# rp2040-mlx90393_1.net
KiCad netlist of a schematic drawn in EasyEDA Pro
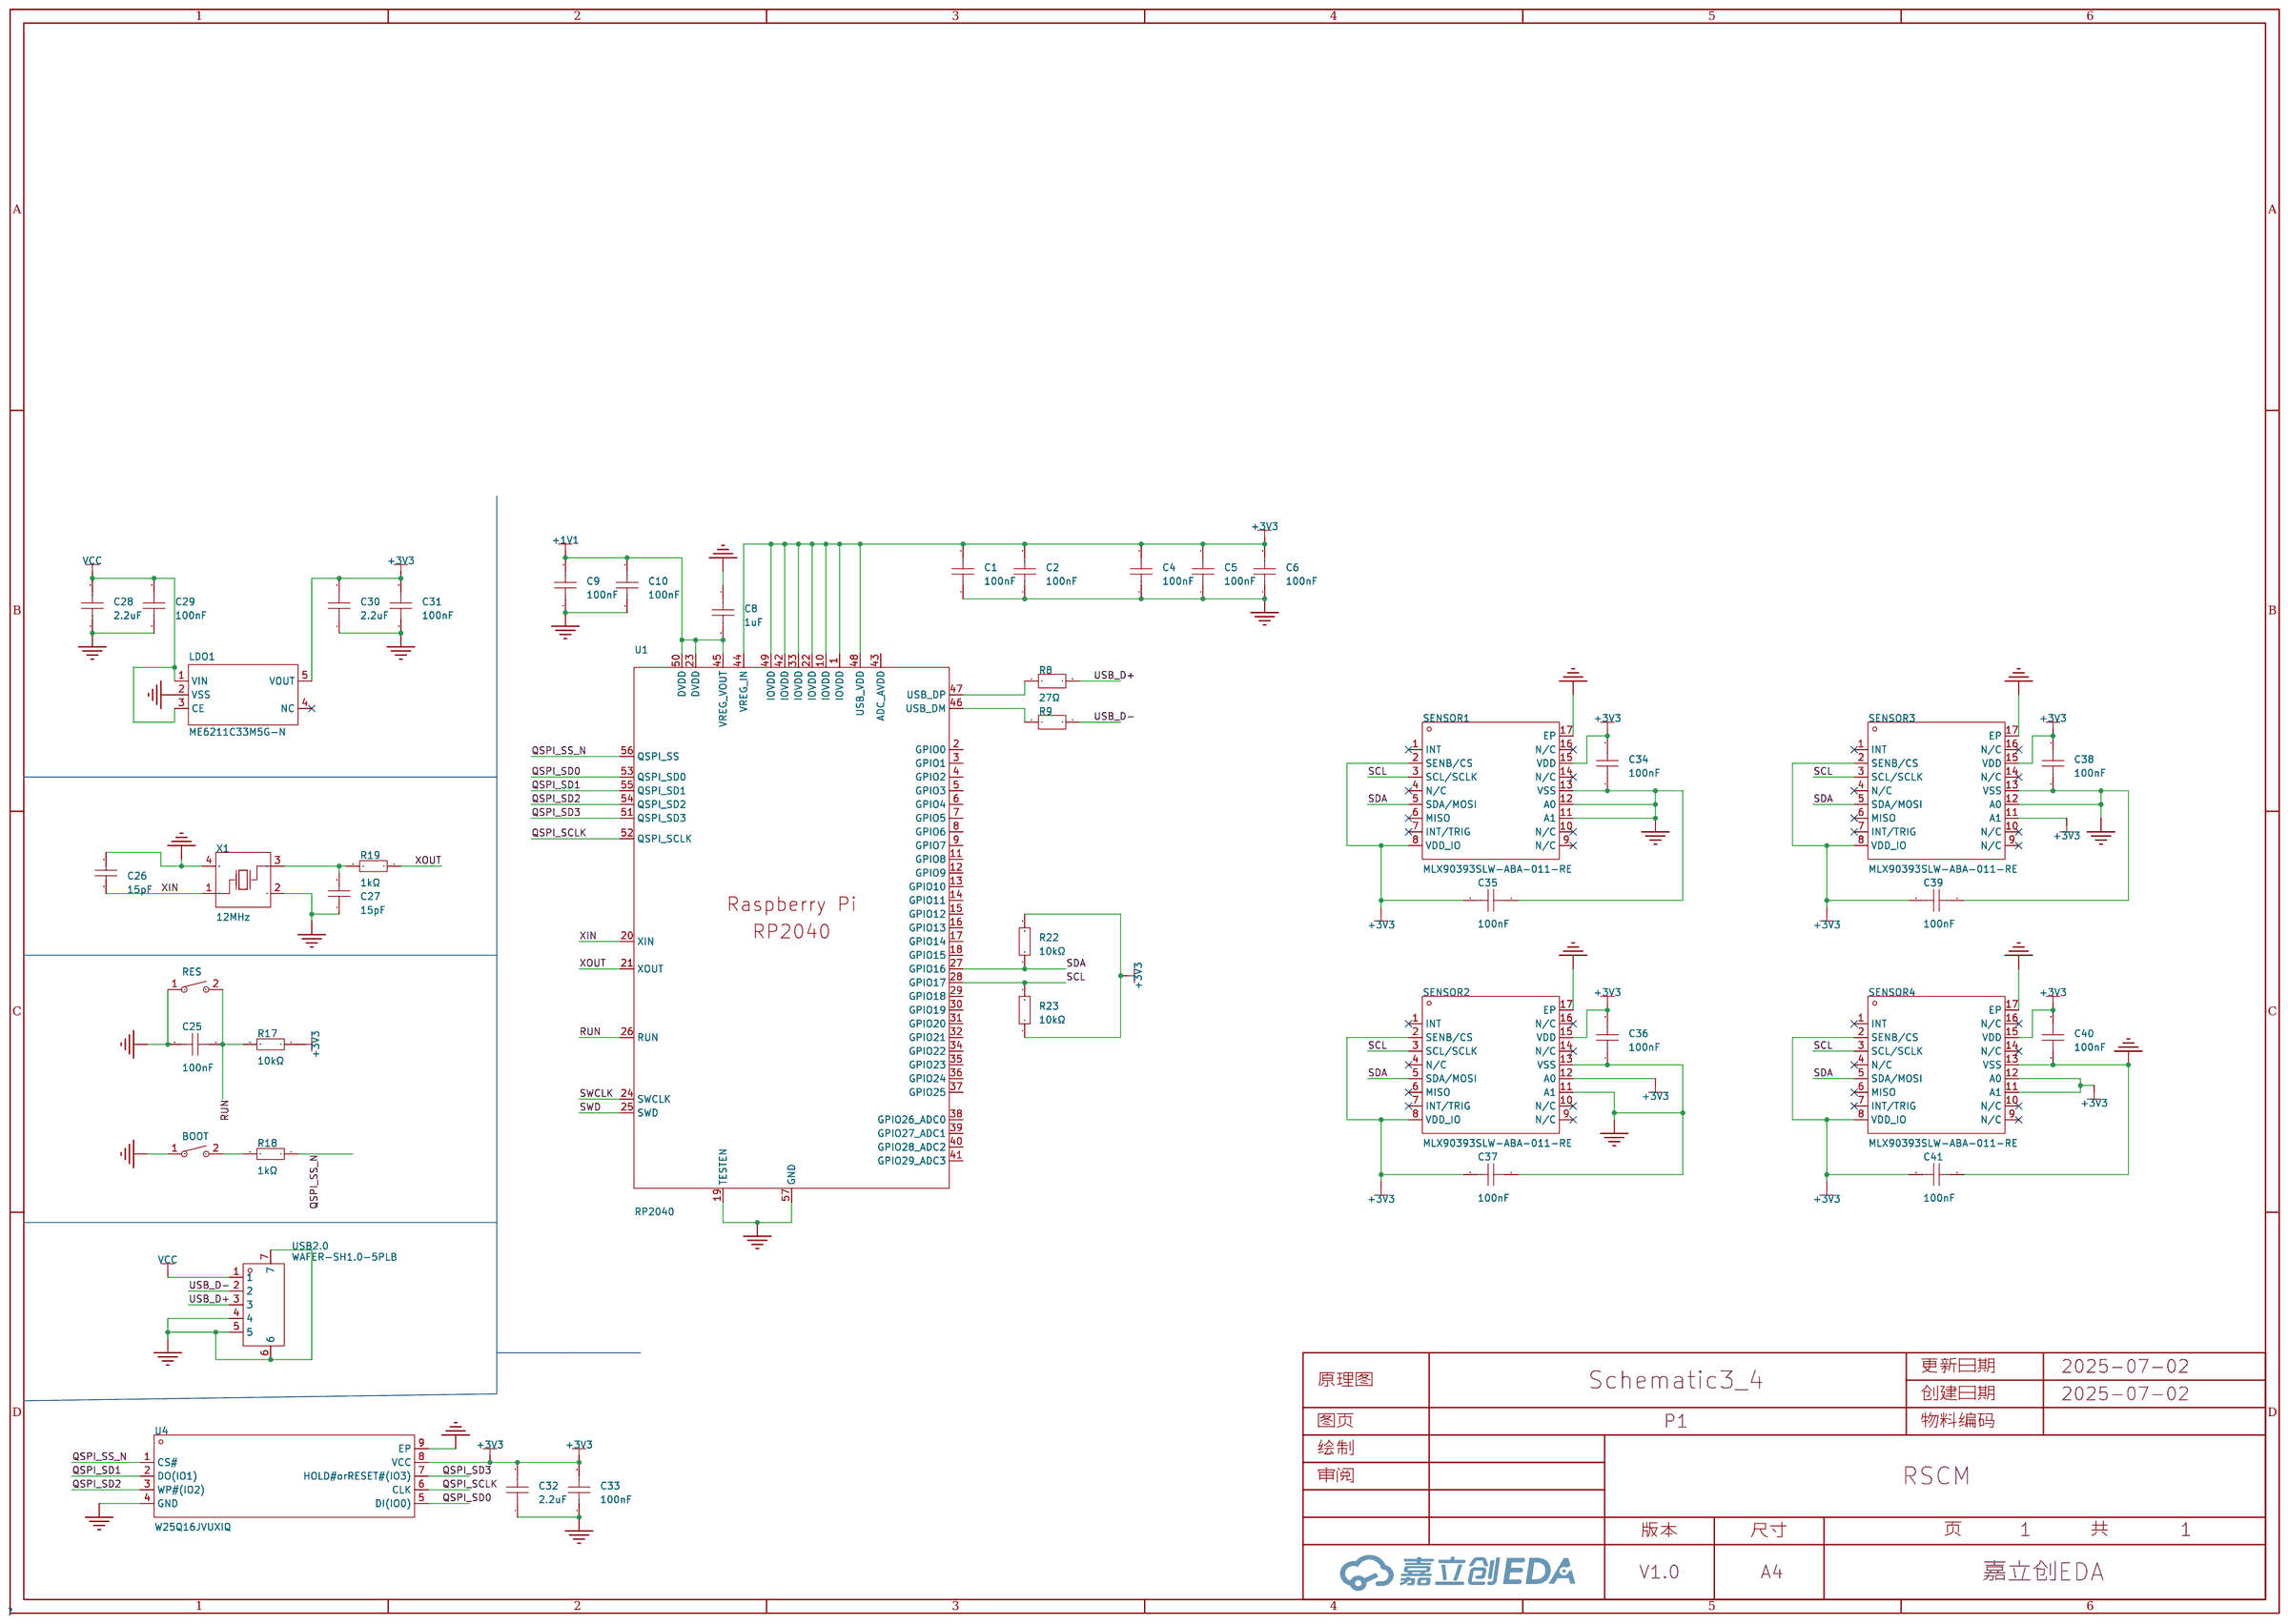
[diagram p0: schematic sheet]

(export (version "E")
  (design (tool "Eeschema 10.0.6"))
  (components
    (comp (ref "BOOT")
      (value "TS-1071AD-A1B3-D4")
      (footprint "easyedapro:SW-SMD_L4.0-W3.0-LS4.8")
      (description "电路结构:单刀单掷;安装方式:-;按钮形状:圆形按钮;带灯:-;作用力:250gf@±30gf;开关长度:4mm;开关宽度:3mm;开关高度:2mm;")
      (fields (field (name "Manufacturer") "Yuandi(元迪)"))
      (libsource (lib "easyedapro") (part "TS-1071AD-A1B3-D4"))
    )
    (comp (ref "C1")
      (value "100nF")
      (footprint "easyedapro:C0603")
      (description "容值:100nF;精度:±10%;额定电压:50V;材质(温度系数):X7R;")
      (fields
        (field (name "Manufacturer Part") "CGA0603X7R104K500JT")
        (field (name "Manufacturer") "HRE(芯声)")
      )
      (libsource (lib "easyedapro") (part "CGA0603X7R104K500JT"))
    )
    (comp (ref "C2")
      (value "100nF")
      (footprint "easyedapro:C0603")
      (description "容值:100nF;精度:±10%;额定电压:50V;材质(温度系数):X7R;")
      (fields
        (field (name "Manufacturer Part") "CGA0603X7R104K500JT")
        (field (name "Manufacturer") "HRE(芯声)")
      )
      (libsource (lib "easyedapro") (part "CGA0603X7R104K500JT"))
    )
    (comp (ref "C4")
      (value "100nF")
      (footprint "easyedapro:C0603")
      (description "容值:100nF;精度:±10%;额定电压:50V;材质(温度系数):X7R;")
      (fields
        (field (name "Manufacturer Part") "CGA0603X7R104K500JT")
        (field (name "Manufacturer") "HRE(芯声)")
      )
      (libsource (lib "easyedapro") (part "CGA0603X7R104K500JT"))
    )
    (comp (ref "C5")
      (value "100nF")
      (footprint "easyedapro:C0603")
      (description "容值:100nF;精度:±10%;额定电压:50V;材质(温度系数):X7R;")
      (fields
        (field (name "Manufacturer Part") "CGA0603X7R104K500JT")
        (field (name "Manufacturer") "HRE(芯声)")
      )
      (libsource (lib "easyedapro") (part "CGA0603X7R104K500JT"))
    )
    (comp (ref "C6")
      (value "100nF")
      (footprint "easyedapro:C0603")
      (description "容值:100nF;精度:±10%;额定电压:50V;材质(温度系数):X7R;")
      (fields
        (field (name "Manufacturer Part") "CGA0603X7R104K500JT")
        (field (name "Manufacturer") "HRE(芯声)")
      )
      (libsource (lib "easyedapro") (part "CGA0603X7R104K500JT"))
    )
    (comp (ref "C8")
      (value "1uF")
      (footprint "easyedapro:C0603")
      (description "容值:1uF;精度:±10%;额定电压:50V;温度系数:X5R;")
      (fields
        (field (name "Manufacturer Part") "CGA0603X5R105K500JT")
        (field (name "Manufacturer") "HRE(芯声)")
      )
      (libsource (lib "easyedapro") (part "CGA0603X5R105K500JT"))
    )
    (comp (ref "C9")
      (value "100nF")
      (footprint "easyedapro:C0603")
      (description "容值:100nF;精度:±10%;额定电压:50V;材质(温度系数):X7R;")
      (fields
        (field (name "Manufacturer Part") "CGA0603X7R104K500JT")
        (field (name "Manufacturer") "HRE(芯声)")
      )
      (libsource (lib "easyedapro") (part "CGA0603X7R104K500JT"))
    )
    (comp (ref "C10")
      (value "100nF")
      (footprint "easyedapro:C0603")
      (description "容值:100nF;精度:±10%;额定电压:50V;材质(温度系数):X7R;")
      (fields
        (field (name "Manufacturer Part") "CGA0603X7R104K500JT")
        (field (name "Manufacturer") "HRE(芯声)")
      )
      (libsource (lib "easyedapro") (part "CGA0603X7R104K500JT"))
    )
    (comp (ref "C25")
      (value "100nF")
      (footprint "easyedapro:C0603")
      (description "容值:100nF;精度:±10%;额定电压:50V;材质(温度系数):X7R;")
      (fields
        (field (name "Manufacturer Part") "CGA0603X7R104K500JT")
        (field (name "Manufacturer") "HRE(芯声)")
      )
      (libsource (lib "easyedapro") (part "CGA0603X7R104K500JT"))
    )
    (comp (ref "C26")
      (value "15pF")
      (footprint "easyedapro:C0603")
      (description "容值:15pF;精度:±5%;额定电压:50V;材质(温度系数):NP0;")
      (fields
        (field (name "Manufacturer Part") "CC0603JRNPO9BN150")
        (field (name "Manufacturer") "YAGEO(国巨)")
      )
      (libsource (lib "easyedapro") (part "CC0603JRNPO9BN150"))
    )
    (comp (ref "C27")
      (value "15pF")
      (footprint "easyedapro:C0603")
      (description "容值:15pF;精度:±5%;额定电压:50V;材质(温度系数):NP0;")
      (fields
        (field (name "Manufacturer Part") "CC0603JRNPO9BN150")
        (field (name "Manufacturer") "YAGEO(国巨)")
      )
      (libsource (lib "easyedapro") (part "CC0603JRNPO9BN150"))
    )
    (comp (ref "C28")
      (value "2.2uF")
      (footprint "easyedapro:C0603")
      (description "容值:2.2uF;精度:±10%;额定电压:50V;材质(温度系数):X5R;")
      (fields
        (field (name "Manufacturer Part") "CL10A225KB8NNNC")
        (field (name "Manufacturer") "SAMSUNG(三星)")
      )
      (libsource (lib "easyedapro") (part "CL10A225KB8NNNC"))
    )
    (comp (ref "C29")
      (value "100nF")
      (footprint "easyedapro:C0603")
      (description "容值:100nF;精度:±10%;额定电压:50V;材质(温度系数):X7R;")
      (fields
        (field (name "Manufacturer Part") "CGA0603X7R104K500JT")
        (field (name "Manufacturer") "HRE(芯声)")
      )
      (libsource (lib "easyedapro") (part "CGA0603X7R104K500JT"))
    )
    (comp (ref "C30")
      (value "2.2uF")
      (footprint "easyedapro:C0603")
      (description "容值:2.2uF;精度:±10%;额定电压:50V;材质(温度系数):X5R;")
      (fields
        (field (name "Manufacturer Part") "CL10A225KB8NNNC")
        (field (name "Manufacturer") "SAMSUNG(三星)")
      )
      (libsource (lib "easyedapro") (part "CL10A225KB8NNNC"))
    )
    (comp (ref "C31")
      (value "100nF")
      (footprint "easyedapro:C0603")
      (description "容值:100nF;精度:±10%;额定电压:50V;材质(温度系数):X7R;")
      (fields
        (field (name "Manufacturer Part") "CGA0603X7R104K500JT")
        (field (name "Manufacturer") "HRE(芯声)")
      )
      (libsource (lib "easyedapro") (part "CGA0603X7R104K500JT"))
    )
    (comp (ref "C32")
      (value "2.2uF")
      (footprint "easyedapro:C0603")
      (description "容值:2.2uF;精度:±10%;额定电压:50V;材质(温度系数):X5R;")
      (fields
        (field (name "Manufacturer Part") "CL10A225KB8NNNC")
        (field (name "Manufacturer") "SAMSUNG(三星)")
      )
      (libsource (lib "easyedapro") (part "CL10A225KB8NNNC"))
    )
    (comp (ref "C33")
      (value "100nF")
      (footprint "easyedapro:C0603")
      (description "容值:100nF;精度:±10%;额定电压:50V;材质(温度系数):X7R;")
      (fields
        (field (name "Manufacturer Part") "CGA0603X7R104K500JT")
        (field (name "Manufacturer") "HRE(芯声)")
      )
      (libsource (lib "easyedapro") (part "CGA0603X7R104K500JT"))
    )
    (comp (ref "C34")
      (value "100nF")
      (footprint "easyedapro:C0603")
      (description "容值:100nF;精度:±10%;额定电压:50V;材质(温度系数):X7R;")
      (fields
        (field (name "Manufacturer Part") "CGA0603X7R104K500JT")
        (field (name "Manufacturer") "HRE(芯声)")
      )
      (libsource (lib "easyedapro") (part "CGA0603X7R104K500JT"))
    )
    (comp (ref "C35")
      (value "100nF")
      (footprint "easyedapro:C0603")
      (description "容值:100nF;精度:±10%;额定电压:50V;材质(温度系数):X7R;")
      (fields
        (field (name "Manufacturer Part") "CGA0603X7R104K500JT")
        (field (name "Manufacturer") "HRE(芯声)")
      )
      (libsource (lib "easyedapro") (part "CGA0603X7R104K500JT"))
    )
    (comp (ref "C36")
      (value "100nF")
      (footprint "easyedapro:C0603")
      (description "容值:100nF;精度:±10%;额定电压:50V;材质(温度系数):X7R;")
      (fields
        (field (name "Manufacturer Part") "CGA0603X7R104K500JT")
        (field (name "Manufacturer") "HRE(芯声)")
      )
      (libsource (lib "easyedapro") (part "CGA0603X7R104K500JT"))
    )
    (comp (ref "C37")
      (value "100nF")
      (footprint "easyedapro:C0603")
      (description "容值:100nF;精度:±10%;额定电压:50V;材质(温度系数):X7R;")
      (fields
        (field (name "Manufacturer Part") "CGA0603X7R104K500JT")
        (field (name "Manufacturer") "HRE(芯声)")
      )
      (libsource (lib "easyedapro") (part "CGA0603X7R104K500JT"))
    )
    (comp (ref "C38")
      (value "100nF")
      (footprint "easyedapro:C0603")
      (description "容值:100nF;精度:±10%;额定电压:50V;材质(温度系数):X7R;")
      (fields
        (field (name "Manufacturer Part") "CGA0603X7R104K500JT")
        (field (name "Manufacturer") "HRE(芯声)")
      )
      (libsource (lib "easyedapro") (part "CGA0603X7R104K500JT"))
    )
    (comp (ref "C39")
      (value "100nF")
      (footprint "easyedapro:C0603")
      (description "容值:100nF;精度:±10%;额定电压:50V;材质(温度系数):X7R;")
      (fields
        (field (name "Manufacturer Part") "CGA0603X7R104K500JT")
        (field (name "Manufacturer") "HRE(芯声)")
      )
      (libsource (lib "easyedapro") (part "CGA0603X7R104K500JT"))
    )
    (comp (ref "C40")
      (value "100nF")
      (footprint "easyedapro:C0603")
      (description "容值:100nF;精度:±10%;额定电压:50V;材质(温度系数):X7R;")
      (fields
        (field (name "Manufacturer Part") "CGA0603X7R104K500JT")
        (field (name "Manufacturer") "HRE(芯声)")
      )
      (libsource (lib "easyedapro") (part "CGA0603X7R104K500JT"))
    )
    (comp (ref "C41")
      (value "100nF")
      (footprint "easyedapro:C0603")
      (description "容值:100nF;精度:±10%;额定电压:50V;材质(温度系数):X7R;")
      (fields
        (field (name "Manufacturer Part") "CGA0603X7R104K500JT")
        (field (name "Manufacturer") "HRE(芯声)")
      )
      (libsource (lib "easyedapro") (part "CGA0603X7R104K500JT"))
    )
    (comp (ref "LDO1")
      (value "ME6211C33M5G-N")
      (footprint "easyedapro:SOT-23-5_L3.0-W1.7-P0.95-LS2.8-BL")
      (description "输出类型:固定;工作电压:6V;输出电压:3.3V;输出电流:500mA;电源纹波抑制比(PSRR):70dB@(1kHz)；62dB@(10kHz);输出极性:正极;")
      (fields (field (name "Manufacturer") "MICRONE(南京微盟)"))
      (libsource (lib "easyedapro") (part "ME6211C33M5G-N"))
    )
    (comp (ref "R8")
      (value "27Ω")
      (footprint "easyedapro:R0603")
      (description "电阻类型:厚膜电阻;阻值:27Ω;精度:±1%;功率:100mW;工作电压:75V;温度系数:±100ppm/°C;")
      (fields (field (name "Manufacturer Part") "FRC0603F27R0TS") (field (name "Manufacturer") "FOJAN(富捷)"))
      (libsource (lib "easyedapro") (part "FRC0603F27R0TS"))
    )
    (comp (ref "R9")
      (value "27Ω")
      (footprint "easyedapro:R0603")
      (description "电阻类型:厚膜电阻;阻值:27Ω;精度:±1%;功率:100mW;工作电压:75V;温度系数:±100ppm/°C;")
      (fields (field (name "Manufacturer Part") "FRC0603F27R0TS") (field (name "Manufacturer") "FOJAN(富捷)"))
      (libsource (lib "easyedapro") (part "FRC0603F27R0TS"))
    )
    (comp (ref "R17")
      (value "10kΩ")
      (footprint "easyedapro:R0603")
      (description "电阻类型:厚膜电阻;阻值:10kΩ;精度:±1%;功率:100mW;")
      (fields (field (name "Manufacturer Part") "RC0603FR-0710KL") (field (name "Manufacturer") "YAGEO(国巨)"))
      (libsource (lib "easyedapro") (part "RC0603FR-0710KL"))
    )
    (comp (ref "R18")
      (value "1kΩ")
      (footprint "easyedapro:R0603")
      (description "电阻类型:厚膜电阻;阻值:10kΩ;精度:±1%;功率:100mW;")
      (fields (field (name "Manufacturer Part") "RC0603FR-0710KL") (field (name "Manufacturer") "YAGEO(国巨)"))
      (libsource (lib "easyedapro") (part "RC0603FR-0710KL"))
    )
    (comp (ref "R19")
      (value "1kΩ")
      (footprint "easyedapro:R0603")
      (description "电阻类型:厚膜电阻;阻值:1kΩ;精度:±1%;功率:100mW;最大工作电压:75V;温度系数:±100ppm/°C;")
      (fields
        (field (name "Manufacturer Part") "0603WAF1001T5E")
        (field (name "Manufacturer") "UNI-ROYAL(厚声)")
      )
      (libsource (lib "easyedapro") (part "0603WAF1001T5E"))
    )
    (comp (ref "R22")
      (value "10kΩ")
      (footprint "easyedapro:R0603")
      (description "电阻类型:厚膜电阻;阻值:4.7kΩ;精度:±1%;功率:100mW;最大工作电压:75V;温度系数:±100ppm/°C;")
      (fields
        (field (name "Manufacturer Part") "0603WAF4701T5E")
        (field (name "Manufacturer") "UNI-ROYAL(厚声)")
      )
      (libsource (lib "easyedapro") (part "0603WAF4701T5E"))
    )
    (comp (ref "R23")
      (value "10kΩ")
      (footprint "easyedapro:R0603")
      (description "电阻类型:厚膜电阻;阻值:4.7kΩ;精度:±1%;功率:100mW;最大工作电压:75V;温度系数:±100ppm/°C;")
      (fields
        (field (name "Manufacturer Part") "0603WAF4701T5E")
        (field (name "Manufacturer") "UNI-ROYAL(厚声)")
      )
      (libsource (lib "easyedapro") (part "0603WAF4701T5E"))
    )
    (comp (ref "RES")
      (value "TS-1071AD-A1B3-D4")
      (footprint "easyedapro:SW-SMD_L4.0-W3.0-LS4.8")
      (description "电路结构:单刀单掷;安装方式:-;按钮形状:圆形按钮;带灯:-;作用力:250gf@±30gf;开关长度:4mm;开关宽度:3mm;开关高度:2mm;")
      (fields (field (name "Manufacturer") "Yuandi(元迪)"))
      (libsource (lib "easyedapro") (part "TS-1071AD-A1B3-D4"))
    )
    (comp (ref "SENSOR1")
      (value "MLX90393SLW-ABA-011-RE")
      (footprint "easyedapro:VQFN-16_L3.0-W3.0-P0.50-BL-EP1.7")
      (description "三轴磁传感器")
      (fields (field (name "Manufacturer") "Melexis(比利时迈来芯)"))
      (libsource (lib "easyedapro") (part "MLX90393SLW-ABA-011-RE"))
    )
    (comp (ref "SENSOR2")
      (value "MLX90393SLW-ABA-011-RE")
      (footprint "easyedapro:VQFN-16_L3.0-W3.0-P0.50-BL-EP1.7")
      (description "三轴磁传感器")
      (fields (field (name "Manufacturer") "Melexis(比利时迈来芯)"))
      (libsource (lib "easyedapro") (part "MLX90393SLW-ABA-011-RE"))
    )
    (comp (ref "SENSOR3")
      (value "MLX90393SLW-ABA-011-RE")
      (footprint "easyedapro:VQFN-16_L3.0-W3.0-P0.50-BL-EP1.7")
      (description "三轴磁传感器")
      (fields (field (name "Manufacturer") "Melexis(比利时迈来芯)"))
      (libsource (lib "easyedapro") (part "MLX90393SLW-ABA-011-RE"))
    )
    (comp (ref "SENSOR4")
      (value "MLX90393SLW-ABA-011-RE")
      (footprint "easyedapro:VQFN-16_L3.0-W3.0-P0.50-BL-EP1.7")
      (description "三轴磁传感器")
      (fields (field (name "Manufacturer") "Melexis(比利时迈来芯)"))
      (libsource (lib "easyedapro") (part "MLX90393SLW-ABA-011-RE"))
    )
    (comp (ref "U1")
      (value "RP2040")
      (footprint "easyedapro:LQFN-56_L7.0-W7.0-P0.4-EP")
      (description "CPU内核:-;CPU最大主频:133MHz;应用领域:-;")
      (fields (field (name "Manufacturer") "Raspberry Pi(树莓派)"))
      (libsource (lib "easyedapro") (part "RP2040"))
    )
    (comp (ref "U4")
      (value "W25Q16JVUXIQ")
      (footprint "easyedapro:USON-8_L3.0-W2.0-P0.50-BL-EP")
      (fields (field (name "Manufacturer") "WINBOND(华邦)"))
      (libsource (lib "easyedapro") (part "W25Q16JVUXIQ"))
    )
    (comp (ref "USB2.0")
      (value "WAFER-SH1.0-5PLB")
      (footprint "easyedapro:CONN-SMD-5P-P1.00_BM05B-SRSS-TB-LF-SN")
      (fields (field (name "Manufacturer") "XUNPU(讯普)"))
      (libsource (lib "easyedapro") (part "WAFER-SH1.0-5PLB"))
    )
    (comp (ref "X1")
      (value "12MHz")
      (footprint "easyedapro:OSC-SMD_4P-L3.2-W2.5-BL")
      (description "晶振类型:贴片晶振;频率:12MHz;常温频差:±10ppm;外接负载电容:20pF;频率稳定度(全温):±20ppm;")
      (fields (field (name "Manufacturer Part") "X322512MSB4SI") (field (name "Manufacturer") "YXC(扬兴晶振)"))
      (libsource (lib "easyedapro") (part "X322512MSB4SI"))
    )
  )
  (nets
    (net (code "1") (name "+1V1") (class "Default")
      (node (ref "C10") (pin "2") (pinfunction "2_2") (pintype "unspecified"))
      (node (ref "C8") (pin "2") (pinfunction "2_2") (pintype "unspecified"))
      (node (ref "C9") (pin "2") (pinfunction "2_2") (pintype "unspecified"))
      (node (ref "U1") (pin "23") (pinfunction "DVDD_23") (pintype "bidirectional"))
      (node (ref "U1") (pin "45") (pinfunction "VREG_VOUT_45") (pintype "bidirectional"))
      (node (ref "U1") (pin "50") (pinfunction "DVDD_50") (pintype "bidirectional"))
    )
    (net (code "2") (name "+3V3") (class "Default")
      (node (ref "C1") (pin "2") (pinfunction "2_2") (pintype "unspecified"))
      (node (ref "C2") (pin "2") (pinfunction "2_2") (pintype "unspecified"))
      (node (ref "C30") (pin "2") (pinfunction "2_2") (pintype "unspecified"))
      (node (ref "C31") (pin "2") (pinfunction "2_2") (pintype "unspecified"))
      (node (ref "C32") (pin "2") (pinfunction "2_2") (pintype "unspecified"))
      (node (ref "C33") (pin "2") (pinfunction "2_2") (pintype "unspecified"))
      (node (ref "C34") (pin "2") (pinfunction "2_2") (pintype "unspecified"))
      (node (ref "C35") (pin "2") (pinfunction "2_2") (pintype "unspecified"))
      (node (ref "C36") (pin "2") (pinfunction "2_2") (pintype "unspecified"))
      (node (ref "C37") (pin "2") (pinfunction "2_2") (pintype "unspecified"))
      (node (ref "C38") (pin "2") (pinfunction "2_2") (pintype "unspecified"))
      (node (ref "C39") (pin "2") (pinfunction "2_2") (pintype "unspecified"))
      (node (ref "C4") (pin "2") (pinfunction "2_2") (pintype "unspecified"))
      (node (ref "C40") (pin "2") (pinfunction "2_2") (pintype "unspecified"))
      (node (ref "C41") (pin "2") (pinfunction "2_2") (pintype "unspecified"))
      (node (ref "C5") (pin "2") (pinfunction "2_2") (pintype "unspecified"))
      (node (ref "C6") (pin "2") (pinfunction "2_2") (pintype "unspecified"))
      (node (ref "LDO1") (pin "5") (pinfunction "VOUT_5") (pintype "unspecified"))
      (node (ref "R17") (pin "1") (pinfunction "1_1") (pintype "input"))
      (node (ref "R22") (pin "2") (pinfunction "2_2") (pintype "input"))
      (node (ref "R23") (pin "1") (pinfunction "1_1") (pintype "input"))
      (node (ref "SENSOR1") (pin "15") (pinfunction "VDD_15") (pintype "unspecified"))
      (node (ref "SENSOR1") (pin "2") (pinfunction "SENB/CS_2") (pintype "unspecified"))
      (node (ref "SENSOR1") (pin "8") (pinfunction "VDD_IO_8") (pintype "unspecified"))
      (node (ref "SENSOR2") (pin "12") (pinfunction "A0_12") (pintype "unspecified"))
      (node (ref "SENSOR2") (pin "15") (pinfunction "VDD_15") (pintype "unspecified"))
      (node (ref "SENSOR2") (pin "2") (pinfunction "SENB/CS_2") (pintype "unspecified"))
      (node (ref "SENSOR2") (pin "8") (pinfunction "VDD_IO_8") (pintype "unspecified"))
      (node (ref "SENSOR3") (pin "11") (pinfunction "A1_11") (pintype "unspecified"))
      (node (ref "SENSOR3") (pin "15") (pinfunction "VDD_15") (pintype "unspecified"))
      (node (ref "SENSOR3") (pin "2") (pinfunction "SENB/CS_2") (pintype "unspecified"))
      (node (ref "SENSOR3") (pin "8") (pinfunction "VDD_IO_8") (pintype "unspecified"))
      (node (ref "SENSOR4") (pin "11") (pinfunction "A1_11") (pintype "unspecified"))
      (node (ref "SENSOR4") (pin "12") (pinfunction "A0_12") (pintype "unspecified"))
      (node (ref "SENSOR4") (pin "15") (pinfunction "VDD_15") (pintype "unspecified"))
      (node (ref "SENSOR4") (pin "2") (pinfunction "SENB/CS_2") (pintype "unspecified"))
      (node (ref "SENSOR4") (pin "8") (pinfunction "VDD_IO_8") (pintype "unspecified"))
      (node (ref "U1") (pin "1") (pinfunction "IOVDD_1") (pintype "bidirectional"))
      (node (ref "U1") (pin "10") (pinfunction "IOVDD_10") (pintype "bidirectional"))
      (node (ref "U1") (pin "22") (pinfunction "IOVDD_22") (pintype "bidirectional"))
      (node (ref "U1") (pin "33") (pinfunction "IOVDD_33") (pintype "bidirectional"))
      (node (ref "U1") (pin "42") (pinfunction "IOVDD_42") (pintype "bidirectional"))
      (node (ref "U1") (pin "44") (pinfunction "VREG_IN_44") (pintype "bidirectional"))
      (node (ref "U1") (pin "48") (pinfunction "USB_VDD_48") (pintype "bidirectional"))
      (node (ref "U1") (pin "49") (pinfunction "IOVDD_49") (pintype "bidirectional"))
      (node (ref "U4") (pin "8") (pinfunction "VCC_8") (pintype "unspecified"))
    )
    (net (code "3") (name "/QSPI_SCLK") (class "Default")
      (node (ref "U1") (pin "52") (pinfunction "QSPI_SCLK_52") (pintype "output"))
      (node (ref "U4") (pin "6") (pinfunction "CLK_6") (pintype "unspecified"))
    )
    (net (code "4") (name "/QSPI_SD0") (class "Default")
      (node (ref "U1") (pin "53") (pinfunction "QSPI_SD0_53") (pintype "bidirectional"))
      (node (ref "U4") (pin "5") (pinfunction "DI(IO0)_5") (pintype "unspecified"))
    )
    (net (code "5") (name "/QSPI_SD1") (class "Default")
      (node (ref "U1") (pin "55") (pinfunction "QSPI_SD1_55") (pintype "bidirectional"))
      (node (ref "U4") (pin "2") (pinfunction "DO(IO1)_2") (pintype "unspecified"))
    )
    (net (code "6") (name "/QSPI_SD2") (class "Default")
      (node (ref "U1") (pin "54") (pinfunction "QSPI_SD2_54") (pintype "bidirectional"))
      (node (ref "U4") (pin "3") (pinfunction "WP#(IO2)_3") (pintype "unspecified"))
    )
    (net (code "7") (name "/QSPI_SD3") (class "Default")
      (node (ref "U1") (pin "51") (pinfunction "QSPI_SD3_51") (pintype "bidirectional"))
      (node (ref "U4") (pin "7") (pinfunction "HOLD#orRESET#(IO3)_7") (pintype "unspecified"))
    )
    (net (code "8") (name "/QSPI_SS_N") (class "Default")
      (node (ref "R18") (pin "1") (pinfunction "1_1") (pintype "input"))
      (node (ref "U1") (pin "56") (pinfunction "QSPI_SS_56") (pintype "bidirectional"))
      (node (ref "U4") (pin "1") (pinfunction "CS#_1") (pintype "unspecified"))
    )
    (net (code "9") (name "/RUN") (class "Default")
      (node (ref "C25") (pin "2") (pinfunction "2_2") (pintype "unspecified"))
      (node (ref "R17") (pin "2") (pinfunction "2_2") (pintype "input"))
      (node (ref "RES") (pin "2") (pinfunction "2_2") (pintype "input"))
      (node (ref "U1") (pin "26") (pinfunction "RUN_26") (pintype "input"))
    )
    (net (code "10") (name "/SCL") (class "Default")
      (node (ref "R23") (pin "2") (pinfunction "2_2") (pintype "input"))
      (node (ref "SENSOR1") (pin "3") (pinfunction "SCL/SCLK_3") (pintype "unspecified"))
      (node (ref "SENSOR2") (pin "3") (pinfunction "SCL/SCLK_3") (pintype "unspecified"))
      (node (ref "SENSOR3") (pin "3") (pinfunction "SCL/SCLK_3") (pintype "unspecified"))
      (node (ref "SENSOR4") (pin "3") (pinfunction "SCL/SCLK_3") (pintype "unspecified"))
      (node (ref "U1") (pin "28") (pinfunction "GPIO17_28") (pintype "bidirectional"))
    )
    (net (code "11") (name "/SDA") (class "Default")
      (node (ref "R22") (pin "1") (pinfunction "1_1") (pintype "input"))
      (node (ref "SENSOR1") (pin "5") (pinfunction "SDA/MOSI_5") (pintype "unspecified"))
      (node (ref "SENSOR2") (pin "5") (pinfunction "SDA/MOSI_5") (pintype "unspecified"))
      (node (ref "SENSOR3") (pin "5") (pinfunction "SDA/MOSI_5") (pintype "unspecified"))
      (node (ref "SENSOR4") (pin "5") (pinfunction "SDA/MOSI_5") (pintype "unspecified"))
      (node (ref "U1") (pin "27") (pinfunction "GPIO16_27") (pintype "bidirectional"))
    )
    (net (code "12") (name "/SWCLK") (class "Default")
      (node (ref "U1") (pin "24") (pinfunction "SWCLK_24") (pintype "output"))
    )
    (net (code "13") (name "/SWD") (class "Default")
      (node (ref "U1") (pin "25") (pinfunction "SWD_25") (pintype "bidirectional"))
    )
    (net (code "14") (name "/USB_D+") (class "Default")
      (node (ref "R8") (pin "2") (pinfunction "2_2") (pintype "unspecified"))
      (node (ref "USB2.0") (pin "3") (pinfunction "3_3") (pintype "unspecified"))
    )
    (net (code "15") (name "/USB_D-") (class "Default")
      (node (ref "R9") (pin "2") (pinfunction "2_2") (pintype "unspecified"))
      (node (ref "USB2.0") (pin "2") (pinfunction "2_2") (pintype "unspecified"))
    )
    (net (code "16") (name "/XIN") (class "Default")
      (node (ref "C26") (pin "1") (pinfunction "1_1") (pintype "input"))
      (node (ref "U1") (pin "20") (pinfunction "XIN_20") (pintype "input"))
      (node (ref "X1") (pin "1") (pinfunction "OSC1_1") (pintype "unspecified"))
    )
    (net (code "17") (name "/XOUT") (class "Default")
      (node (ref "R19") (pin "1") (pinfunction "1_1") (pintype "input"))
      (node (ref "U1") (pin "21") (pinfunction "XOUT_21") (pintype "unspecified"))
    )
    (net (code "18") (name "GND") (class "Default")
      (node (ref "BOOT") (pin "1") (pinfunction "1_1") (pintype "input"))
      (node (ref "C1") (pin "1") (pinfunction "1_1") (pintype "unspecified"))
      (node (ref "C10") (pin "1") (pinfunction "1_1") (pintype "unspecified"))
      (node (ref "C2") (pin "1") (pinfunction "1_1") (pintype "unspecified"))
      (node (ref "C25") (pin "1") (pinfunction "1_1") (pintype "unspecified"))
      (node (ref "C26") (pin "2") (pinfunction "2_2") (pintype "input"))
      (node (ref "C27") (pin "1") (pinfunction "1_1") (pintype "input"))
      (node (ref "C28") (pin "1") (pinfunction "1_1") (pintype "unspecified"))
      (node (ref "C29") (pin "1") (pinfunction "1_1") (pintype "unspecified"))
      (node (ref "C30") (pin "1") (pinfunction "1_1") (pintype "unspecified"))
      (node (ref "C31") (pin "1") (pinfunction "1_1") (pintype "unspecified"))
      (node (ref "C32") (pin "1") (pinfunction "1_1") (pintype "unspecified"))
      (node (ref "C33") (pin "1") (pinfunction "1_1") (pintype "unspecified"))
      (node (ref "C34") (pin "1") (pinfunction "1_1") (pintype "unspecified"))
      (node (ref "C35") (pin "1") (pinfunction "1_1") (pintype "unspecified"))
      (node (ref "C36") (pin "1") (pinfunction "1_1") (pintype "unspecified"))
      (node (ref "C37") (pin "1") (pinfunction "1_1") (pintype "unspecified"))
      (node (ref "C38") (pin "1") (pinfunction "1_1") (pintype "unspecified"))
      (node (ref "C39") (pin "1") (pinfunction "1_1") (pintype "unspecified"))
      (node (ref "C4") (pin "1") (pinfunction "1_1") (pintype "unspecified"))
      (node (ref "C40") (pin "1") (pinfunction "1_1") (pintype "unspecified"))
      (node (ref "C41") (pin "1") (pinfunction "1_1") (pintype "unspecified"))
      (node (ref "C5") (pin "1") (pinfunction "1_1") (pintype "unspecified"))
      (node (ref "C6") (pin "1") (pinfunction "1_1") (pintype "unspecified"))
      (node (ref "C8") (pin "1") (pinfunction "1_1") (pintype "unspecified"))
      (node (ref "C9") (pin "1") (pinfunction "1_1") (pintype "unspecified"))
      (node (ref "LDO1") (pin "2") (pinfunction "VSS_2") (pintype "unspecified"))
      (node (ref "RES") (pin "1") (pinfunction "1_1") (pintype "input"))
      (node (ref "SENSOR1") (pin "11") (pinfunction "A1_11") (pintype "unspecified"))
      (node (ref "SENSOR1") (pin "12") (pinfunction "A0_12") (pintype "unspecified"))
      (node (ref "SENSOR1") (pin "13") (pinfunction "VSS_13") (pintype "unspecified"))
      (node (ref "SENSOR1") (pin "17") (pinfunction "EP_17") (pintype "unspecified"))
      (node (ref "SENSOR2") (pin "11") (pinfunction "A1_11") (pintype "unspecified"))
      (node (ref "SENSOR2") (pin "13") (pinfunction "VSS_13") (pintype "unspecified"))
      (node (ref "SENSOR2") (pin "17") (pinfunction "EP_17") (pintype "unspecified"))
      (node (ref "SENSOR3") (pin "12") (pinfunction "A0_12") (pintype "unspecified"))
      (node (ref "SENSOR3") (pin "13") (pinfunction "VSS_13") (pintype "unspecified"))
      (node (ref "SENSOR3") (pin "17") (pinfunction "EP_17") (pintype "unspecified"))
      (node (ref "SENSOR4") (pin "13") (pinfunction "VSS_13") (pintype "unspecified"))
      (node (ref "SENSOR4") (pin "17") (pinfunction "EP_17") (pintype "unspecified"))
      (node (ref "U1") (pin "19") (pinfunction "TESTEN_19") (pintype "unspecified"))
      (node (ref "U1") (pin "57") (pinfunction "GND_57") (pintype "bidirectional"))
      (node (ref "U4") (pin "4") (pinfunction "GND_4") (pintype "unspecified"))
      (node (ref "U4") (pin "9") (pinfunction "EP_9") (pintype "unspecified"))
      (node (ref "USB2.0") (pin "4") (pinfunction "4_4") (pintype "unspecified"))
      (node (ref "USB2.0") (pin "5") (pinfunction "5_5") (pintype "unspecified"))
      (node (ref "USB2.0") (pin "6") (pinfunction "6_6") (pintype "unspecified"))
      (node (ref "USB2.0") (pin "7") (pinfunction "7_7") (pintype "unspecified"))
      (node (ref "X1") (pin "2") (pinfunction "GND_2") (pintype "unspecified"))
      (node (ref "X1") (pin "4") (pinfunction "GND_4") (pintype "unspecified"))
    )
    (net (code "19") (name "Net-(BOOT-Pad2)") (class "Default")
      (node (ref "BOOT") (pin "2") (pinfunction "2_2") (pintype "input"))
      (node (ref "R18") (pin "2") (pinfunction "2_2") (pintype "input"))
    )
    (net (code "20") (name "Net-(U1-USB_DM)") (class "Default")
      (node (ref "R9") (pin "1") (pinfunction "1_1") (pintype "unspecified"))
      (node (ref "U1") (pin "46") (pinfunction "USB_DM_46") (pintype "bidirectional"))
    )
    (net (code "21") (name "Net-(U1-USB_DP)") (class "Default")
      (node (ref "R8") (pin "1") (pinfunction "1_1") (pintype "unspecified"))
      (node (ref "U1") (pin "47") (pinfunction "USB_DP_47") (pintype "bidirectional"))
    )
    (net (code "22") (name "Net-(X1-OSC2)") (class "Default")
      (node (ref "C27") (pin "2") (pinfunction "2_2") (pintype "input"))
      (node (ref "R19") (pin "2") (pinfunction "2_2") (pintype "input"))
      (node (ref "X1") (pin "3") (pinfunction "OSC2_3") (pintype "unspecified"))
    )
    (net (code "23") (name "VCC") (class "Default")
      (node (ref "C28") (pin "2") (pinfunction "2_2") (pintype "unspecified"))
      (node (ref "C29") (pin "2") (pinfunction "2_2") (pintype "unspecified"))
      (node (ref "LDO1") (pin "1") (pinfunction "VIN_1") (pintype "unspecified"))
      (node (ref "LDO1") (pin "3") (pinfunction "CE_3") (pintype "unspecified"))
      (node (ref "USB2.0") (pin "1") (pinfunction "1_1") (pintype "unspecified"))
    )
    (net (code "24") (name "unconnected-(LDO1-NC-Pad4)") (class "Default")
      (node (ref "LDO1") (pin "4") (pinfunction "NC_4") (pintype "unspecified+no_connect"))
    )
    (net (code "25") (name "unconnected-(SENSOR1-INT-Pad1)") (class "Default")
      (node (ref "SENSOR1") (pin "1") (pinfunction "INT_1") (pintype "unspecified+no_connect"))
    )
    (net (code "26") (name "unconnected-(SENSOR1-INT{slash}TRIG-Pad7)") (class "Default")
      (node (ref "SENSOR1") (pin "7") (pinfunction "INT/TRIG_7") (pintype "unspecified+no_connect"))
    )
    (net (code "27") (name "unconnected-(SENSOR1-MISO-Pad6)") (class "Default")
      (node (ref "SENSOR1") (pin "6") (pinfunction "MISO_6") (pintype "unspecified+no_connect"))
    )
    (net (code "28") (name "unconnected-(SENSOR1-N{slash}C-Pad4)") (class "Default")
      (node (ref "SENSOR1") (pin "4") (pinfunction "N/C_4") (pintype "unspecified+no_connect"))
    )
    (net (code "29") (name "unconnected-(SENSOR1-N{slash}C-Pad9)") (class "Default")
      (node (ref "SENSOR1") (pin "9") (pinfunction "N/C_9") (pintype "unspecified+no_connect"))
    )
    (net (code "30") (name "unconnected-(SENSOR1-N{slash}C-Pad10)") (class "Default")
      (node (ref "SENSOR1") (pin "10") (pinfunction "N/C_10") (pintype "unspecified+no_connect"))
    )
    (net (code "31") (name "unconnected-(SENSOR1-N{slash}C-Pad14)") (class "Default")
      (node (ref "SENSOR1") (pin "14") (pinfunction "N/C_14") (pintype "unspecified+no_connect"))
    )
    (net (code "32") (name "unconnected-(SENSOR1-N{slash}C-Pad16)") (class "Default")
      (node (ref "SENSOR1") (pin "16") (pinfunction "N/C_16") (pintype "unspecified+no_connect"))
    )
    (net (code "33") (name "unconnected-(SENSOR2-INT-Pad1)") (class "Default")
      (node (ref "SENSOR2") (pin "1") (pinfunction "INT_1") (pintype "unspecified+no_connect"))
    )
    (net (code "34") (name "unconnected-(SENSOR2-INT{slash}TRIG-Pad7)") (class "Default")
      (node (ref "SENSOR2") (pin "7") (pinfunction "INT/TRIG_7") (pintype "unspecified+no_connect"))
    )
    (net (code "35") (name "unconnected-(SENSOR2-MISO-Pad6)") (class "Default")
      (node (ref "SENSOR2") (pin "6") (pinfunction "MISO_6") (pintype "unspecified+no_connect"))
    )
    (net (code "36") (name "unconnected-(SENSOR2-N{slash}C-Pad4)") (class "Default")
      (node (ref "SENSOR2") (pin "4") (pinfunction "N/C_4") (pintype "unspecified+no_connect"))
    )
    (net (code "37") (name "unconnected-(SENSOR2-N{slash}C-Pad9)") (class "Default")
      (node (ref "SENSOR2") (pin "9") (pinfunction "N/C_9") (pintype "unspecified+no_connect"))
    )
    (net (code "38") (name "unconnected-(SENSOR2-N{slash}C-Pad10)") (class "Default")
      (node (ref "SENSOR2") (pin "10") (pinfunction "N/C_10") (pintype "unspecified+no_connect"))
    )
    (net (code "39") (name "unconnected-(SENSOR2-N{slash}C-Pad14)") (class "Default")
      (node (ref "SENSOR2") (pin "14") (pinfunction "N/C_14") (pintype "unspecified+no_connect"))
    )
    (net (code "40") (name "unconnected-(SENSOR2-N{slash}C-Pad16)") (class "Default")
      (node (ref "SENSOR2") (pin "16") (pinfunction "N/C_16") (pintype "unspecified+no_connect"))
    )
    (net (code "41") (name "unconnected-(SENSOR3-INT-Pad1)") (class "Default")
      (node (ref "SENSOR3") (pin "1") (pinfunction "INT_1") (pintype "unspecified+no_connect"))
    )
    (net (code "42") (name "unconnected-(SENSOR3-INT{slash}TRIG-Pad7)") (class "Default")
      (node (ref "SENSOR3") (pin "7") (pinfunction "INT/TRIG_7") (pintype "unspecified+no_connect"))
    )
    (net (code "43") (name "unconnected-(SENSOR3-MISO-Pad6)") (class "Default")
      (node (ref "SENSOR3") (pin "6") (pinfunction "MISO_6") (pintype "unspecified+no_connect"))
    )
    (net (code "44") (name "unconnected-(SENSOR3-N{slash}C-Pad4)") (class "Default")
      (node (ref "SENSOR3") (pin "4") (pinfunction "N/C_4") (pintype "unspecified+no_connect"))
    )
    (net (code "45") (name "unconnected-(SENSOR3-N{slash}C-Pad9)") (class "Default")
      (node (ref "SENSOR3") (pin "9") (pinfunction "N/C_9") (pintype "unspecified+no_connect"))
    )
    (net (code "46") (name "unconnected-(SENSOR3-N{slash}C-Pad10)") (class "Default")
      (node (ref "SENSOR3") (pin "10") (pinfunction "N/C_10") (pintype "unspecified+no_connect"))
    )
    (net (code "47") (name "unconnected-(SENSOR3-N{slash}C-Pad14)") (class "Default")
      (node (ref "SENSOR3") (pin "14") (pinfunction "N/C_14") (pintype "unspecified+no_connect"))
    )
    (net (code "48") (name "unconnected-(SENSOR3-N{slash}C-Pad16)") (class "Default")
      (node (ref "SENSOR3") (pin "16") (pinfunction "N/C_16") (pintype "unspecified+no_connect"))
    )
    (net (code "49") (name "unconnected-(SENSOR4-INT-Pad1)") (class "Default")
      (node (ref "SENSOR4") (pin "1") (pinfunction "INT_1") (pintype "unspecified+no_connect"))
    )
    (net (code "50") (name "unconnected-(SENSOR4-INT{slash}TRIG-Pad7)") (class "Default")
      (node (ref "SENSOR4") (pin "7") (pinfunction "INT/TRIG_7") (pintype "unspecified+no_connect"))
    )
    (net (code "51") (name "unconnected-(SENSOR4-MISO-Pad6)") (class "Default")
      (node (ref "SENSOR4") (pin "6") (pinfunction "MISO_6") (pintype "unspecified+no_connect"))
    )
    (net (code "52") (name "unconnected-(SENSOR4-N{slash}C-Pad4)") (class "Default")
      (node (ref "SENSOR4") (pin "4") (pinfunction "N/C_4") (pintype "unspecified+no_connect"))
    )
    (net (code "53") (name "unconnected-(SENSOR4-N{slash}C-Pad9)") (class "Default")
      (node (ref "SENSOR4") (pin "9") (pinfunction "N/C_9") (pintype "unspecified+no_connect"))
    )
    (net (code "54") (name "unconnected-(SENSOR4-N{slash}C-Pad10)") (class "Default")
      (node (ref "SENSOR4") (pin "10") (pinfunction "N/C_10") (pintype "unspecified+no_connect"))
    )
    (net (code "55") (name "unconnected-(SENSOR4-N{slash}C-Pad14)") (class "Default")
      (node (ref "SENSOR4") (pin "14") (pinfunction "N/C_14") (pintype "unspecified+no_connect"))
    )
    (net (code "56") (name "unconnected-(SENSOR4-N{slash}C-Pad16)") (class "Default")
      (node (ref "SENSOR4") (pin "16") (pinfunction "N/C_16") (pintype "unspecified+no_connect"))
    )
    (net (code "57") (name "unconnected-(U1-ADC_AVDD-Pad43)") (class "Default")
      (node (ref "U1") (pin "43") (pinfunction "ADC_AVDD_43") (pintype "bidirectional"))
    )
    (net (code "58") (name "unconnected-(U1-GPIO0-Pad2)") (class "Default")
      (node (ref "U1") (pin "2") (pinfunction "GPIO0_2") (pintype "bidirectional"))
    )
    (net (code "59") (name "unconnected-(U1-GPIO1-Pad3)") (class "Default")
      (node (ref "U1") (pin "3") (pinfunction "GPIO1_3") (pintype "bidirectional"))
    )
    (net (code "60") (name "unconnected-(U1-GPIO2-Pad4)") (class "Default")
      (node (ref "U1") (pin "4") (pinfunction "GPIO2_4") (pintype "bidirectional"))
    )
    (net (code "61") (name "unconnected-(U1-GPIO3-Pad5)") (class "Default")
      (node (ref "U1") (pin "5") (pinfunction "GPIO3_5") (pintype "bidirectional"))
    )
    (net (code "62") (name "unconnected-(U1-GPIO4-Pad6)") (class "Default")
      (node (ref "U1") (pin "6") (pinfunction "GPIO4_6") (pintype "bidirectional"))
    )
    (net (code "63") (name "unconnected-(U1-GPIO5-Pad7)") (class "Default")
      (node (ref "U1") (pin "7") (pinfunction "GPIO5_7") (pintype "bidirectional"))
    )
    (net (code "64") (name "unconnected-(U1-GPIO6-Pad8)") (class "Default")
      (node (ref "U1") (pin "8") (pinfunction "GPIO6_8") (pintype "bidirectional"))
    )
    (net (code "65") (name "unconnected-(U1-GPIO7-Pad9)") (class "Default")
      (node (ref "U1") (pin "9") (pinfunction "GPIO7_9") (pintype "bidirectional"))
    )
    (net (code "66") (name "unconnected-(U1-GPIO8-Pad11)") (class "Default")
      (node (ref "U1") (pin "11") (pinfunction "GPIO8_11") (pintype "bidirectional"))
    )
    (net (code "67") (name "unconnected-(U1-GPIO9-Pad12)") (class "Default")
      (node (ref "U1") (pin "12") (pinfunction "GPIO9_12") (pintype "bidirectional"))
    )
    (net (code "68") (name "unconnected-(U1-GPIO10-Pad13)") (class "Default")
      (node (ref "U1") (pin "13") (pinfunction "GPIO10_13") (pintype "bidirectional"))
    )
    (net (code "69") (name "unconnected-(U1-GPIO11-Pad14)") (class "Default")
      (node (ref "U1") (pin "14") (pinfunction "GPIO11_14") (pintype "bidirectional"))
    )
    (net (code "70") (name "unconnected-(U1-GPIO12-Pad15)") (class "Default")
      (node (ref "U1") (pin "15") (pinfunction "GPIO12_15") (pintype "bidirectional"))
    )
    (net (code "71") (name "unconnected-(U1-GPIO13-Pad16)") (class "Default")
      (node (ref "U1") (pin "16") (pinfunction "GPIO13_16") (pintype "bidirectional"))
    )
    (net (code "72") (name "unconnected-(U1-GPIO14-Pad17)") (class "Default")
      (node (ref "U1") (pin "17") (pinfunction "GPIO14_17") (pintype "bidirectional"))
    )
    (net (code "73") (name "unconnected-(U1-GPIO15-Pad18)") (class "Default")
      (node (ref "U1") (pin "18") (pinfunction "GPIO15_18") (pintype "bidirectional"))
    )
    (net (code "74") (name "unconnected-(U1-GPIO18-Pad29)") (class "Default")
      (node (ref "U1") (pin "29") (pinfunction "GPIO18_29") (pintype "bidirectional"))
    )
    (net (code "75") (name "unconnected-(U1-GPIO19-Pad30)") (class "Default")
      (node (ref "U1") (pin "30") (pinfunction "GPIO19_30") (pintype "bidirectional"))
    )
    (net (code "76") (name "unconnected-(U1-GPIO20-Pad31)") (class "Default")
      (node (ref "U1") (pin "31") (pinfunction "GPIO20_31") (pintype "bidirectional"))
    )
    (net (code "77") (name "unconnected-(U1-GPIO21-Pad32)") (class "Default")
      (node (ref "U1") (pin "32") (pinfunction "GPIO21_32") (pintype "bidirectional"))
    )
    (net (code "78") (name "unconnected-(U1-GPIO22-Pad34)") (class "Default")
      (node (ref "U1") (pin "34") (pinfunction "GPIO22_34") (pintype "bidirectional"))
    )
    (net (code "79") (name "unconnected-(U1-GPIO23-Pad35)") (class "Default")
      (node (ref "U1") (pin "35") (pinfunction "GPIO23_35") (pintype "bidirectional"))
    )
    (net (code "80") (name "unconnected-(U1-GPIO24-Pad36)") (class "Default")
      (node (ref "U1") (pin "36") (pinfunction "GPIO24_36") (pintype "bidirectional"))
    )
    (net (code "81") (name "unconnected-(U1-GPIO25-Pad37)") (class "Default")
      (node (ref "U1") (pin "37") (pinfunction "GPIO25_37") (pintype "bidirectional"))
    )
    (net (code "82") (name "unconnected-(U1-GPIO26_ADC0-Pad38)") (class "Default")
      (node (ref "U1") (pin "38") (pinfunction "GPIO26_ADC0_38") (pintype "bidirectional"))
    )
    (net (code "83") (name "unconnected-(U1-GPIO27_ADC1-Pad39)") (class "Default")
      (node (ref "U1") (pin "39") (pinfunction "GPIO27_ADC1_39") (pintype "bidirectional"))
    )
    (net (code "84") (name "unconnected-(U1-GPIO28_ADC2-Pad40)") (class "Default")
      (node (ref "U1") (pin "40") (pinfunction "GPIO28_ADC2_40") (pintype "bidirectional"))
    )
    (net (code "85") (name "unconnected-(U1-GPIO29_ADC3-Pad41)") (class "Default")
      (node (ref "U1") (pin "41") (pinfunction "GPIO29_ADC3_41") (pintype "bidirectional"))
    )
  )
)
